# vestibular.net
KiCad netlist of a schematic drawn in EAGLE
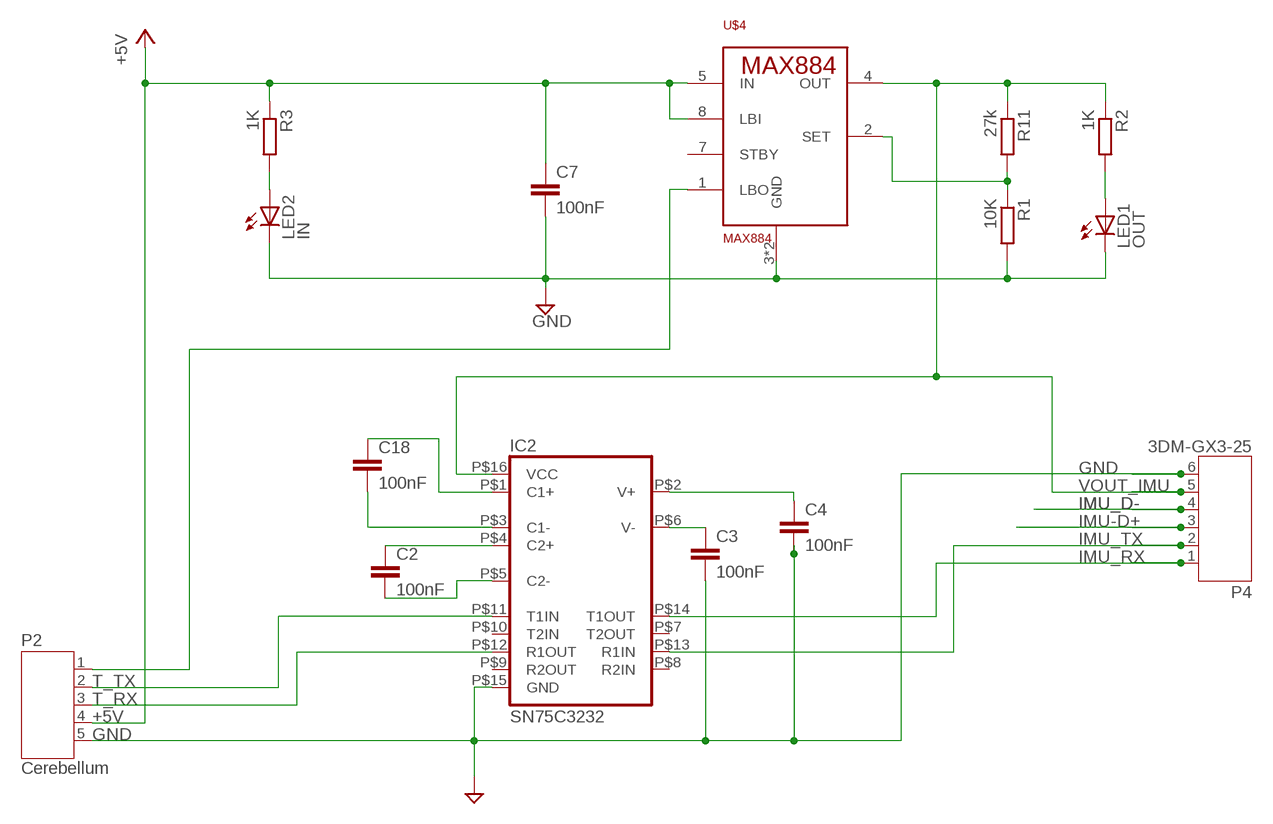
[diagram p0: schematic, sheet 1]

(export (version "E")
  (design (tool "Eeschema 10.0.6"))
  (components
    (comp (ref "C2")
      (value "100nF")
      (footprint "eagle-import:C025-025X050")
      (libsource (lib "eagle-import") (part "C-EU025-025X050"))
    )
    (comp (ref "C3")
      (value "100nF")
      (footprint "eagle-import:C025-025X050")
      (libsource (lib "eagle-import") (part "C-EU025-025X050"))
    )
    (comp (ref "C4")
      (value "100nF")
      (footprint "eagle-import:C025-025X050")
      (libsource (lib "eagle-import") (part "C-EU025-025X050"))
    )
    (comp (ref "C7")
      (value "100nF")
      (footprint "eagle-import:C025-025X050")
      (libsource (lib "eagle-import") (part "C-EU025-025X050"))
    )
    (comp (ref "C18")
      (value "100nF")
      (footprint "eagle-import:C025-025X050")
      (libsource (lib "eagle-import") (part "C-EU025-025X050"))
    )
    (comp (ref "IC2")
      (value "SN75C3232")
      (footprint "eagle-import:SOIC16")
      (fields (field (name "MF") "Maxim Integrated") (field (name "MP") "MAX3232"))
      (libsource (lib "eagle-import") (part "MAX3232"))
    )
    (comp (ref "LED1")
      (value "OUT")
      (footprint "eagle-import:LED3MM")
      (libsource (lib "eagle-import") (part "LED3MM"))
    )
    (comp (ref "LED2")
      (value "IN")
      (footprint "eagle-import:LED3MM")
      (libsource (lib "eagle-import") (part "LED3MM"))
    )
    (comp (ref "P2")
      (value "Cerebellum")
      (footprint "eagle-import:JST-PH5")
      (libsource (lib "eagle-import") (part "JST-PH5"))
    )
    (comp (ref "P4")
      (value "3DM-GX3-25")
      (footprint "eagle-import:JST-PH6")
      (libsource (lib "eagle-import") (part "JST-PH6"))
    )
    (comp (ref "R1")
      (value "10K")
      (footprint "eagle-import:0204_7")
      (libsource (lib "eagle-import") (part "R-EU_0204/7"))
    )
    (comp (ref "R2")
      (value "1K")
      (footprint "eagle-import:0204_7")
      (libsource (lib "eagle-import") (part "R-EU_0204/7"))
    )
    (comp (ref "R3")
      (value "1K")
      (footprint "eagle-import:0204_7")
      (libsource (lib "eagle-import") (part "R-EU_0204/7"))
    )
    (comp (ref "R11")
      (value "27k")
      (footprint "eagle-import:0204_7")
      (libsource (lib "eagle-import") (part "R-EU_0204/7"))
    )
    (comp (ref "U$4")
      (value "MAX884")
      (footprint "eagle-import:SO08")
      (libsource (lib "eagle-import") (part "MAX884"))
    )
  )
  (nets
    (net (code "1") (name "+5V") (class "Default")
      (node (ref "C7") (pin "1") (pinfunction "1_1") (pintype "passive"))
      (node (ref "P2") (pin "4") (pinfunction "4_4") (pintype "passive"))
      (node (ref "R3") (pin "1") (pinfunction "1_1") (pintype "passive"))
      (node (ref "U$4") (pin "5") (pinfunction "IN_5") (pintype "bidirectional"))
      (node (ref "U$4") (pin "8") (pinfunction "LBI_8") (pintype "bidirectional"))
    )
    (net (code "2") (name "/IMU-D+") (class "Default")
      (node (ref "P4") (pin "3") (pinfunction "3_3") (pintype "passive"))
    )
    (net (code "3") (name "/IMU_D-") (class "Default")
      (node (ref "P4") (pin "4") (pinfunction "4_4") (pintype "passive"))
    )
    (net (code "4") (name "/IMU_RX") (class "Default")
      (node (ref "IC2") (pin "P$14") (pinfunction "T1OUT_P$14") (pintype "output"))
      (node (ref "P4") (pin "1") (pinfunction "1_1") (pintype "passive"))
    )
    (net (code "5") (name "/IMU_TX") (class "Default")
      (node (ref "IC2") (pin "P$13") (pinfunction "R1IN_P$13") (pintype "input"))
      (node (ref "P4") (pin "2") (pinfunction "2_2") (pintype "passive"))
    )
    (net (code "6") (name "/T_RX") (class "Default")
      (node (ref "IC2") (pin "P$12") (pinfunction "R1OUT_P$12") (pintype "output"))
      (node (ref "P2") (pin "3") (pinfunction "3_3") (pintype "passive"))
    )
    (net (code "7") (name "/T_TX") (class "Default")
      (node (ref "IC2") (pin "P$11") (pinfunction "T1IN_P$11") (pintype "input"))
      (node (ref "P2") (pin "2") (pinfunction "2_2") (pintype "passive"))
    )
    (net (code "8") (name "/VOUT_IMU") (class "Default")
      (node (ref "IC2") (pin "P$16") (pinfunction "VCC_P$16") (pintype "power_in"))
      (node (ref "P4") (pin "5") (pinfunction "5_5") (pintype "passive"))
      (node (ref "R11") (pin "1") (pinfunction "1_1") (pintype "passive"))
      (node (ref "R2") (pin "1") (pinfunction "1_1") (pintype "passive"))
      (node (ref "U$4") (pin "4") (pinfunction "OUT_4") (pintype "bidirectional"))
    )
    (net (code "9") (name "GND") (class "Default")
      (node (ref "C3") (pin "2") (pinfunction "2_2") (pintype "passive"))
      (node (ref "C4") (pin "2") (pinfunction "2_2") (pintype "passive"))
      (node (ref "C7") (pin "2") (pinfunction "2_2") (pintype "passive"))
      (node (ref "IC2") (pin "P$15") (pinfunction "GND_P$15") (pintype "power_in"))
      (node (ref "LED1") (pin "K") (pinfunction "C_K") (pintype "passive"))
      (node (ref "LED2") (pin "K") (pinfunction "C_K") (pintype "passive"))
      (node (ref "P2") (pin "5") (pinfunction "5_5") (pintype "passive"))
      (node (ref "P4") (pin "6") (pinfunction "6_6") (pintype "passive"))
      (node (ref "R1") (pin "2") (pinfunction "2_2") (pintype "passive"))
      (node (ref "U$4") (pin "3") (pinfunction "GND_3") (pintype "bidirectional"))
      (node (ref "U$4") (pin "6") (pinfunction "GND_6") (pintype "bidirectional"))
    )
    (net (code "10") (name "Net-(IC2-C1+)") (class "Default")
      (node (ref "C18") (pin "1") (pinfunction "1_1") (pintype "passive"))
      (node (ref "IC2") (pin "P$1") (pinfunction "C1+_P$1") (pintype "passive"))
    )
    (net (code "11") (name "Net-(IC2-C1-)") (class "Default")
      (node (ref "C18") (pin "2") (pinfunction "2_2") (pintype "passive"))
      (node (ref "IC2") (pin "P$3") (pinfunction "C1-_P$3") (pintype "passive"))
    )
    (net (code "12") (name "Net-(IC2-C2+)") (class "Default")
      (node (ref "C2") (pin "1") (pinfunction "1_1") (pintype "passive"))
      (node (ref "IC2") (pin "P$4") (pinfunction "C2+_P$4") (pintype "passive"))
    )
    (net (code "13") (name "Net-(IC2-C2-)") (class "Default")
      (node (ref "C2") (pin "2") (pinfunction "2_2") (pintype "passive"))
      (node (ref "IC2") (pin "P$5") (pinfunction "C2-_P$5") (pintype "passive"))
    )
    (net (code "14") (name "Net-(IC2-V+)") (class "Default")
      (node (ref "C4") (pin "1") (pinfunction "1_1") (pintype "passive"))
      (node (ref "IC2") (pin "P$2") (pinfunction "V+_P$2") (pintype "passive"))
    )
    (net (code "15") (name "Net-(IC2-V-)") (class "Default")
      (node (ref "C3") (pin "1") (pinfunction "1_1") (pintype "passive"))
      (node (ref "IC2") (pin "P$6") (pinfunction "V-_P$6") (pintype "passive"))
    )
    (net (code "16") (name "Net-(LED1-PadA)") (class "Default")
      (node (ref "LED1") (pin "A") (pinfunction "A_A") (pintype "passive"))
      (node (ref "R2") (pin "2") (pinfunction "2_2") (pintype "passive"))
    )
    (net (code "17") (name "Net-(LED2-PadA)") (class "Default")
      (node (ref "LED2") (pin "A") (pinfunction "A_A") (pintype "passive"))
      (node (ref "R3") (pin "2") (pinfunction "2_2") (pintype "passive"))
    )
    (net (code "18") (name "Net-(U$4-LBO)") (class "Default")
      (node (ref "P2") (pin "1") (pinfunction "1_1") (pintype "passive"))
      (node (ref "U$4") (pin "1") (pinfunction "LBO_1") (pintype "bidirectional"))
    )
    (net (code "19") (name "Net-(U$4-SET)") (class "Default")
      (node (ref "R1") (pin "1") (pinfunction "1_1") (pintype "passive"))
      (node (ref "R11") (pin "2") (pinfunction "2_2") (pintype "passive"))
      (node (ref "U$4") (pin "2") (pinfunction "SET_2") (pintype "bidirectional"))
    )
    (net (code "20") (name "unconnected-(IC2-R2IN-PadP$8)") (class "Default")
      (node (ref "IC2") (pin "P$8") (pinfunction "R2IN_P$8") (pintype "input"))
    )
    (net (code "21") (name "unconnected-(IC2-R2OUT-PadP$9)") (class "Default")
      (node (ref "IC2") (pin "P$9") (pinfunction "R2OUT_P$9") (pintype "output"))
    )
    (net (code "22") (name "unconnected-(IC2-T2IN-PadP$10)") (class "Default")
      (node (ref "IC2") (pin "P$10") (pinfunction "T2IN_P$10") (pintype "input"))
    )
    (net (code "23") (name "unconnected-(IC2-T2OUT-PadP$7)") (class "Default")
      (node (ref "IC2") (pin "P$7") (pinfunction "T2OUT_P$7") (pintype "output"))
    )
    (net (code "24") (name "unconnected-(U$4-STBY-Pad7)") (class "Default")
      (node (ref "U$4") (pin "7") (pinfunction "STBY_7") (pintype "bidirectional"))
    )
  )
)
